# 06_MSM8916_EBIO_LPDDR3.net
KiCad netlist of a schematic drawn in Altium Designer
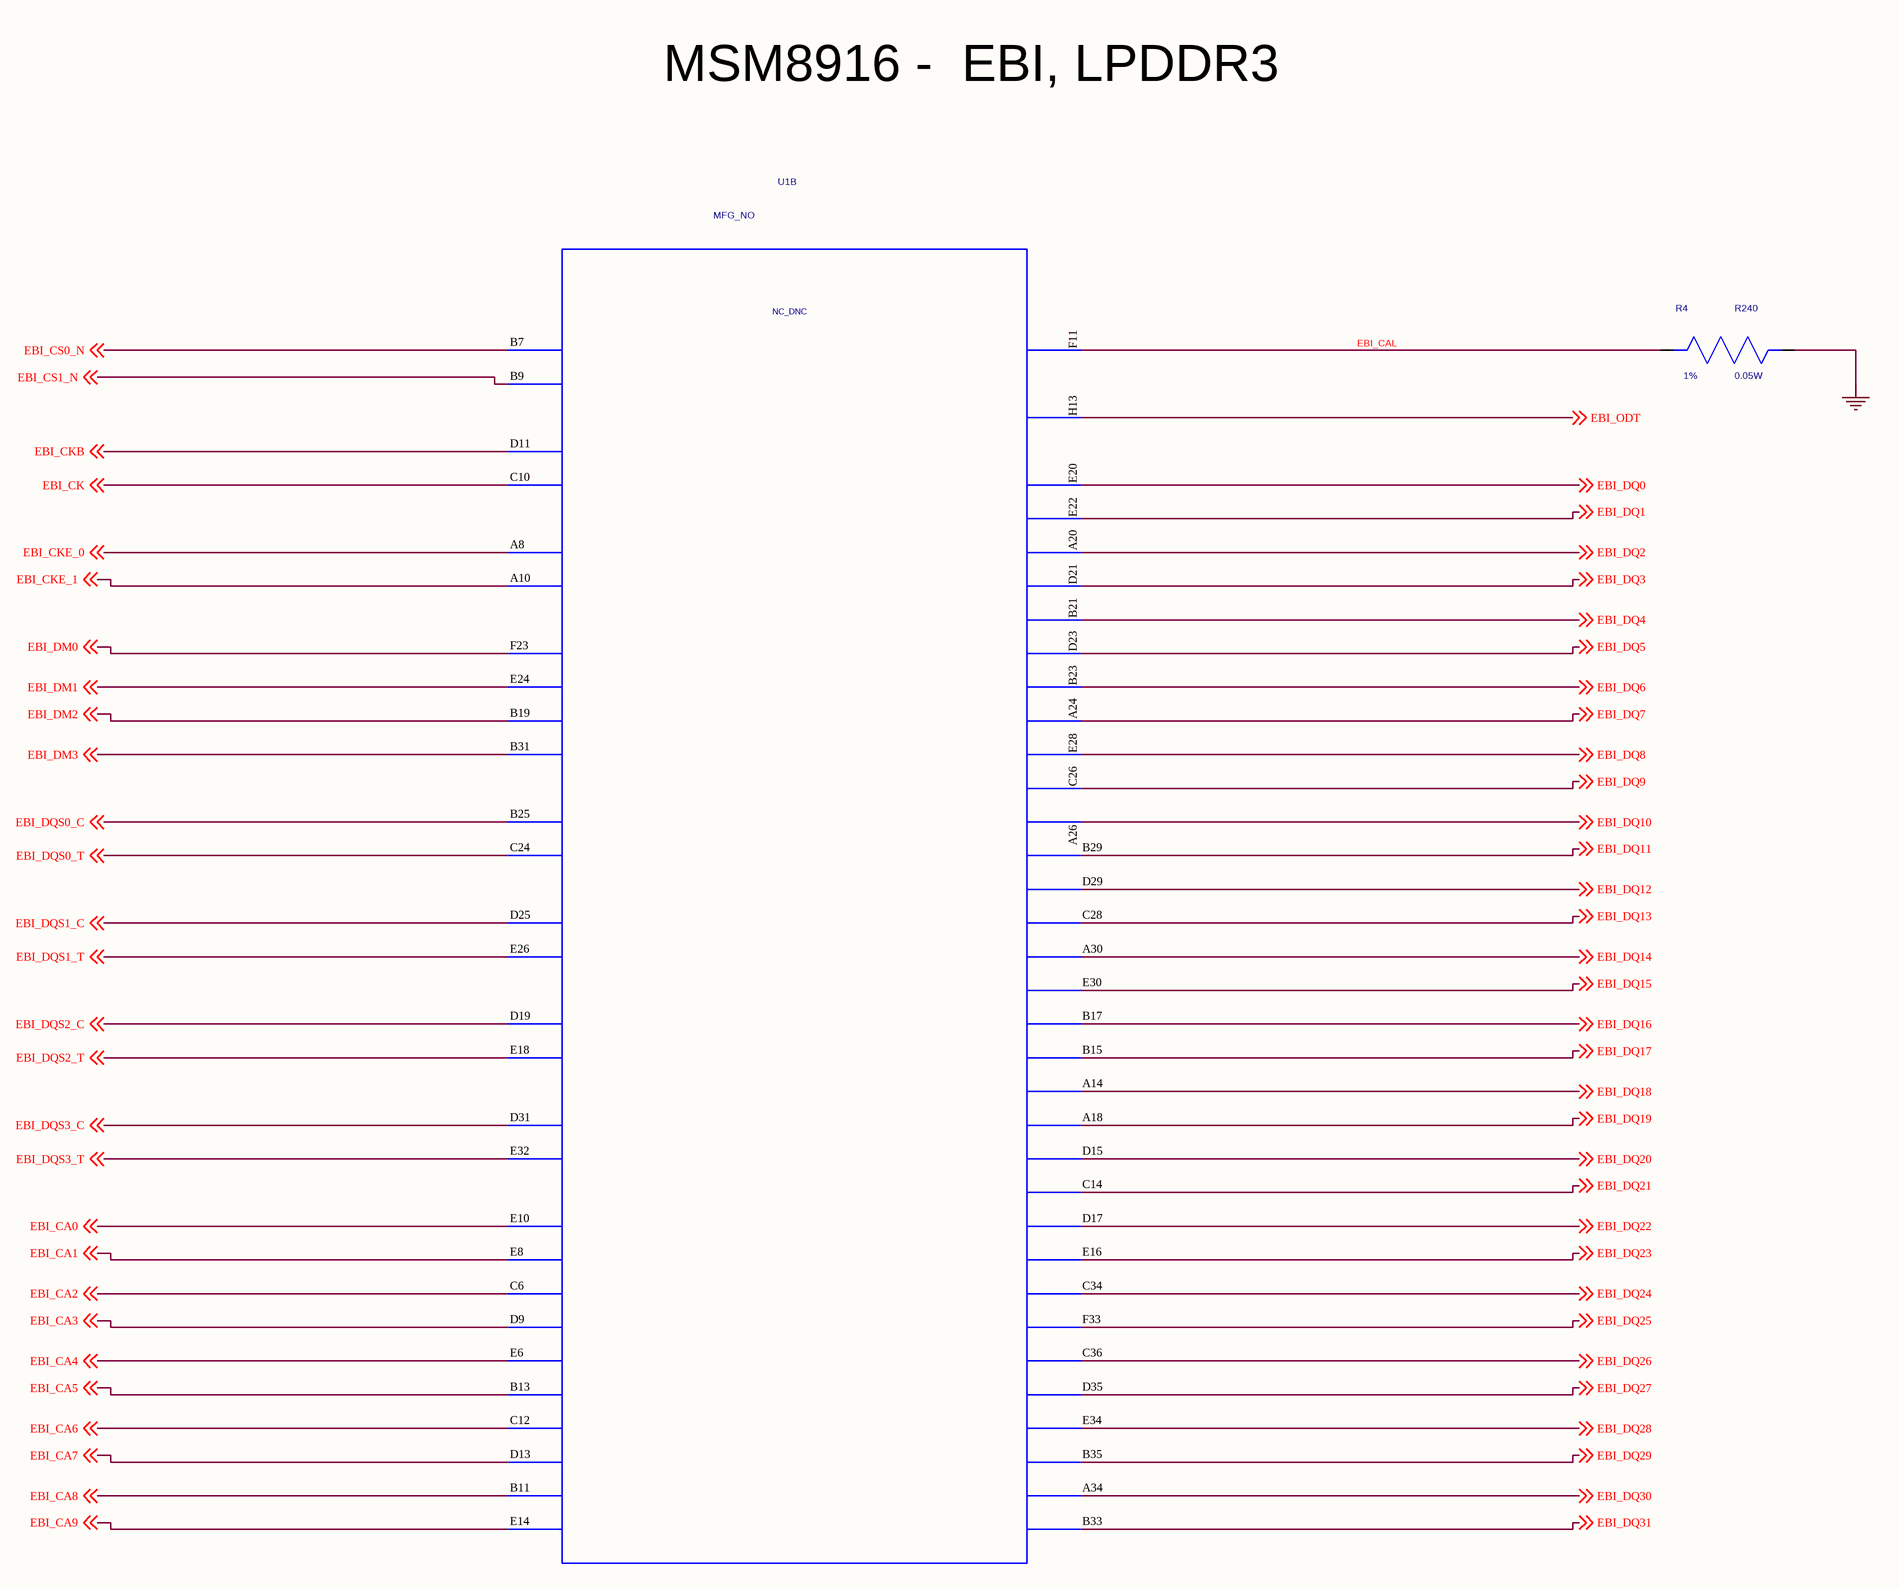
[diagram p0: 06_MSM8916_EBIO LPDDR3.SchDoc, top left]
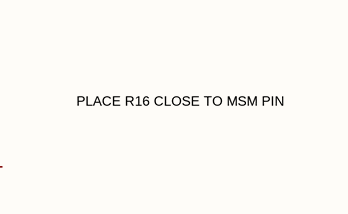
[diagram p1: 06_MSM8916_EBIO LPDDR3.SchDoc, top right]
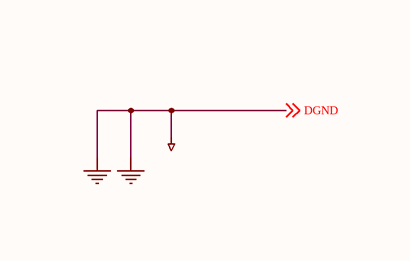
[diagram p2: 06_MSM8916_EBIO LPDDR3.SchDoc, bottom left]
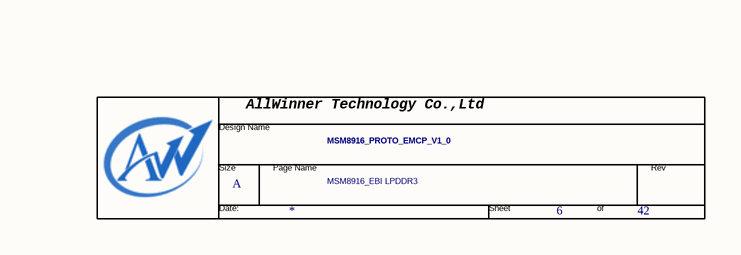
[diagram p3: 06_MSM8916_EBIO LPDDR3.SchDoc, bottom right]

(export (version "E")
  (design (tool "Eeschema 10.0.6"))
  (components
    (comp (ref "*")
      (value "TitleBlock0-AW")
      (fields
        (field (name "PAGE COUNT") "42")
        (field (name "PAGE NUMBER") "6")
        (field (name "PAGE SIZE") "A")
        (field (name "TITLE") "MSM8916_PROTO_EMCP_V1_0")
        (field (name "DOC") "MSM8916_EBI LPDDR3")
      )
      (libsource (lib "*") (part "TitleBlock0-AW"))
    )
    (comp (ref "R4")
      (value "R240")
      (fields
        (field (name "TOLERANCE") "1%")
        (field (name "POWER") "0.05W")
        (field (name "PART_NUMBER") "MCN_NO")
      )
      (libsource (lib "MSM8916_DRAM_PMIC_REF_Library") (part "RESISTOR_Dup3"))
    )
    (comp (ref "U1")
      (value "ASIC_MSM8936_760PIN")
      (footprint "MSM-8916-0-760NSP-TR-00-0")
      (fields
        (field (name "SYMNAME") "NC_DNC")
        (field (name "PART_NUMBER") "MCN_NO")
        (field (name "PART_ID") "MFG_NO")
      )
      (libsource (lib "MSM8916_DRAM_PMIC_REF_Library") (part "ASIC_MSM8936_760PIN"))
    )
  )
  (nets
    (net (code "1") (name "/EBI_CAL") (class "Default")
      (node (ref "R4") (pin "1") (pinfunction "POS_1") (pintype "bidirectional"))
      (node (ref "U1") (pin "F11") (pinfunction "EBI0_CAL_F11") (pintype "bidirectional"))
    )
    (net (code "2") (name "DGND") (class "Default")
      (node (ref "R4") (pin "2") (pinfunction "NEG_2") (pintype "bidirectional"))
    )
    (net (code "3") (name "EBI_CA0") (class "Default")
      (node (ref "U1") (pin "E10") (pinfunction "EBI0_CA_0_E10") (pintype "bidirectional"))
    )
    (net (code "4") (name "EBI_CA1") (class "Default")
      (node (ref "U1") (pin "E8") (pinfunction "EBI0_CA_1_E8") (pintype "bidirectional"))
    )
    (net (code "5") (name "EBI_CA2") (class "Default")
      (node (ref "U1") (pin "C6") (pinfunction "EBI0_CA_2_C6") (pintype "bidirectional"))
    )
    (net (code "6") (name "EBI_CA3") (class "Default")
      (node (ref "U1") (pin "D9") (pinfunction "EBI0_CA_3_D9") (pintype "bidirectional"))
    )
    (net (code "7") (name "EBI_CA4") (class "Default")
      (node (ref "U1") (pin "E6") (pinfunction "EBI0_CA_4_E6") (pintype "bidirectional"))
    )
    (net (code "8") (name "EBI_CA5") (class "Default")
      (node (ref "U1") (pin "B13") (pinfunction "EBI0_CA_5_B13") (pintype "bidirectional"))
    )
    (net (code "9") (name "EBI_CA6") (class "Default")
      (node (ref "U1") (pin "C12") (pinfunction "EBI0_CA_6_C12") (pintype "bidirectional"))
    )
    (net (code "10") (name "EBI_CA7") (class "Default")
      (node (ref "U1") (pin "D13") (pinfunction "EBI0_CA_7_D13") (pintype "bidirectional"))
    )
    (net (code "11") (name "EBI_CA8") (class "Default")
      (node (ref "U1") (pin "B11") (pinfunction "EBI0_CA_8_B11") (pintype "bidirectional"))
    )
    (net (code "12") (name "EBI_CA9") (class "Default")
      (node (ref "U1") (pin "E14") (pinfunction "EBI0_CA_9_E14") (pintype "bidirectional"))
    )
    (net (code "13") (name "EBI_CK") (class "Default")
      (node (ref "U1") (pin "C10") (pinfunction "EBI0_CK_C10") (pintype "bidirectional"))
    )
    (net (code "14") (name "EBI_CKB") (class "Default")
      (node (ref "U1") (pin "D11") (pinfunction "EBI0_CKB_D11") (pintype "bidirectional"))
    )
    (net (code "15") (name "EBI_CKE_0") (class "Default")
      (node (ref "U1") (pin "A8") (pinfunction "EBI0_CKE_0_A8") (pintype "bidirectional"))
    )
    (net (code "16") (name "EBI_CKE_1") (class "Default")
      (node (ref "U1") (pin "A10") (pinfunction "EBI0_CKE_1_A10") (pintype "bidirectional"))
    )
    (net (code "17") (name "EBI_CS0_N") (class "Default")
      (node (ref "U1") (pin "B7") (pinfunction "EBI0_CS_N_0_B7") (pintype "bidirectional"))
    )
    (net (code "18") (name "EBI_CS1_N") (class "Default")
      (node (ref "U1") (pin "B9") (pinfunction "EBI0_CS_N_1_B9") (pintype "bidirectional"))
    )
    (net (code "19") (name "EBI_DM0") (class "Default")
      (node (ref "U1") (pin "F23") (pinfunction "EBI0_DM_0_F23") (pintype "bidirectional"))
    )
    (net (code "20") (name "EBI_DM1") (class "Default")
      (node (ref "U1") (pin "E24") (pinfunction "EBI0_DM_1_E24") (pintype "bidirectional"))
    )
    (net (code "21") (name "EBI_DM2") (class "Default")
      (node (ref "U1") (pin "B19") (pinfunction "EBI0_DM_2_B19") (pintype "bidirectional"))
    )
    (net (code "22") (name "EBI_DM3") (class "Default")
      (node (ref "U1") (pin "B31") (pinfunction "EBI0_DM_3_B31") (pintype "bidirectional"))
    )
    (net (code "23") (name "EBI_DQ0") (class "Default")
      (node (ref "U1") (pin "E20") (pinfunction "EBI0_DQ_0_E20") (pintype "bidirectional"))
    )
    (net (code "24") (name "EBI_DQ1") (class "Default")
      (node (ref "U1") (pin "E22") (pinfunction "EBI0_DQ_1_E22") (pintype "bidirectional"))
    )
    (net (code "25") (name "EBI_DQ2") (class "Default")
      (node (ref "U1") (pin "A20") (pinfunction "EBI0_DQ_2_A20") (pintype "bidirectional"))
    )
    (net (code "26") (name "EBI_DQ3") (class "Default")
      (node (ref "U1") (pin "D21") (pinfunction "EBI0_DQ_3_D21") (pintype "bidirectional"))
    )
    (net (code "27") (name "EBI_DQ4") (class "Default")
      (node (ref "U1") (pin "B21") (pinfunction "EBI0_DQ_4_B21") (pintype "bidirectional"))
    )
    (net (code "28") (name "EBI_DQ5") (class "Default")
      (node (ref "U1") (pin "D23") (pinfunction "EBI0_DQ_5_D23") (pintype "bidirectional"))
    )
    (net (code "29") (name "EBI_DQ6") (class "Default")
      (node (ref "U1") (pin "B23") (pinfunction "EBI0_DQ_6_B23") (pintype "bidirectional"))
    )
    (net (code "30") (name "EBI_DQ7") (class "Default")
      (node (ref "U1") (pin "A24") (pinfunction "EBI0_DQ_7_A24") (pintype "bidirectional"))
    )
    (net (code "31") (name "EBI_DQ8") (class "Default")
      (node (ref "U1") (pin "E28") (pinfunction "EBI0_DQ_8_E28") (pintype "bidirectional"))
    )
    (net (code "32") (name "EBI_DQ9") (class "Default")
      (node (ref "U1") (pin "C26") (pinfunction "EBI0_DQ_9_C26") (pintype "bidirectional"))
    )
    (net (code "33") (name "EBI_DQ10") (class "Default")
      (node (ref "U1") (pin "A26") (pinfunction "EBI0_DQ_10_A26") (pintype "bidirectional"))
    )
    (net (code "34") (name "EBI_DQ11") (class "Default")
      (node (ref "U1") (pin "B29") (pinfunction "EBI0_DQ_11_B29") (pintype "bidirectional"))
    )
    (net (code "35") (name "EBI_DQ12") (class "Default")
      (node (ref "U1") (pin "D29") (pinfunction "EBI0_DQ_12_D29") (pintype "bidirectional"))
    )
    (net (code "36") (name "EBI_DQ13") (class "Default")
      (node (ref "U1") (pin "C28") (pinfunction "EBI0_DQ_13_C28") (pintype "bidirectional"))
    )
    (net (code "37") (name "EBI_DQ14") (class "Default")
      (node (ref "U1") (pin "A30") (pinfunction "EBI0_DQ_14_A30") (pintype "bidirectional"))
    )
    (net (code "38") (name "EBI_DQ15") (class "Default")
      (node (ref "U1") (pin "E30") (pinfunction "EBI0_DQ_15_E30") (pintype "bidirectional"))
    )
    (net (code "39") (name "EBI_DQ16") (class "Default")
      (node (ref "U1") (pin "B17") (pinfunction "EBI0_DQ_16_B17") (pintype "bidirectional"))
    )
    (net (code "40") (name "EBI_DQ17") (class "Default")
      (node (ref "U1") (pin "B15") (pinfunction "EBI0_DQ_17_B15") (pintype "bidirectional"))
    )
    (net (code "41") (name "EBI_DQ18") (class "Default")
      (node (ref "U1") (pin "A14") (pinfunction "EBI0_DQ_18_A14") (pintype "bidirectional"))
    )
    (net (code "42") (name "EBI_DQ19") (class "Default")
      (node (ref "U1") (pin "A18") (pinfunction "EBI0_DQ_19_A18") (pintype "bidirectional"))
    )
    (net (code "43") (name "EBI_DQ20") (class "Default")
      (node (ref "U1") (pin "D15") (pinfunction "EBI0_DQ_20_D15") (pintype "bidirectional"))
    )
    (net (code "44") (name "EBI_DQ21") (class "Default")
      (node (ref "U1") (pin "C14") (pinfunction "EBI0_DQ_21_C14") (pintype "bidirectional"))
    )
    (net (code "45") (name "EBI_DQ22") (class "Default")
      (node (ref "U1") (pin "D17") (pinfunction "EBI0_DQ_22_D17") (pintype "bidirectional"))
    )
    (net (code "46") (name "EBI_DQ23") (class "Default")
      (node (ref "U1") (pin "E16") (pinfunction "EBI0_DQ_23_E16") (pintype "bidirectional"))
    )
    (net (code "47") (name "EBI_DQ24") (class "Default")
      (node (ref "U1") (pin "C34") (pinfunction "EBI0_DQ_24_C34") (pintype "bidirectional"))
    )
    (net (code "48") (name "EBI_DQ25") (class "Default")
      (node (ref "U1") (pin "F33") (pinfunction "EBI0_DQ_25_F33") (pintype "bidirectional"))
    )
    (net (code "49") (name "EBI_DQ26") (class "Default")
      (node (ref "U1") (pin "C36") (pinfunction "EBI0_DQ_26_C36") (pintype "bidirectional"))
    )
    (net (code "50") (name "EBI_DQ27") (class "Default")
      (node (ref "U1") (pin "D35") (pinfunction "EBI0_DQ_27_D35") (pintype "bidirectional"))
    )
    (net (code "51") (name "EBI_DQ28") (class "Default")
      (node (ref "U1") (pin "E34") (pinfunction "EBI0_DQ_28_E34") (pintype "bidirectional"))
    )
    (net (code "52") (name "EBI_DQ29") (class "Default")
      (node (ref "U1") (pin "B35") (pinfunction "EBI0_DQ_29_B35") (pintype "bidirectional"))
    )
    (net (code "53") (name "EBI_DQ30") (class "Default")
      (node (ref "U1") (pin "A34") (pinfunction "EBI0_DQ_30_A34") (pintype "bidirectional"))
    )
    (net (code "54") (name "EBI_DQ31") (class "Default")
      (node (ref "U1") (pin "B33") (pinfunction "EBI0_DQ_31_B33") (pintype "bidirectional"))
    )
    (net (code "55") (name "EBI_DQS0_C") (class "Default")
      (node (ref "U1") (pin "B25") (pinfunction "EBI0_DQSB_0_B25") (pintype "bidirectional"))
    )
    (net (code "56") (name "EBI_DQS0_T") (class "Default")
      (node (ref "U1") (pin "C24") (pinfunction "EBI0_DQS_0_C24") (pintype "bidirectional"))
    )
    (net (code "57") (name "EBI_DQS1_C") (class "Default")
      (node (ref "U1") (pin "D25") (pinfunction "EBI0_DQSB_1_D25") (pintype "bidirectional"))
    )
    (net (code "58") (name "EBI_DQS1_T") (class "Default")
      (node (ref "U1") (pin "E26") (pinfunction "EBI0_DQS_1_E26") (pintype "bidirectional"))
    )
    (net (code "59") (name "EBI_DQS2_C") (class "Default")
      (node (ref "U1") (pin "D19") (pinfunction "EBI0_DQSB_2_D19") (pintype "bidirectional"))
    )
    (net (code "60") (name "EBI_DQS2_T") (class "Default")
      (node (ref "U1") (pin "E18") (pinfunction "EBI0_DQS_2_E18") (pintype "bidirectional"))
    )
    (net (code "61") (name "EBI_DQS3_C") (class "Default")
      (node (ref "U1") (pin "D31") (pinfunction "EBI0_DQSB_3_D31") (pintype "bidirectional"))
    )
    (net (code "62") (name "EBI_DQS3_T") (class "Default")
      (node (ref "U1") (pin "E32") (pinfunction "EBI0_DQS_3_E32") (pintype "bidirectional"))
    )
    (net (code "63") (name "EBI_ODT") (class "Default")
      (node (ref "U1") (pin "H13") (pinfunction "EBI0_ODT_H13") (pintype "bidirectional"))
    )
  )
)
